# tps92512.net
KiCad netlist of a schematic drawn in EAGLE
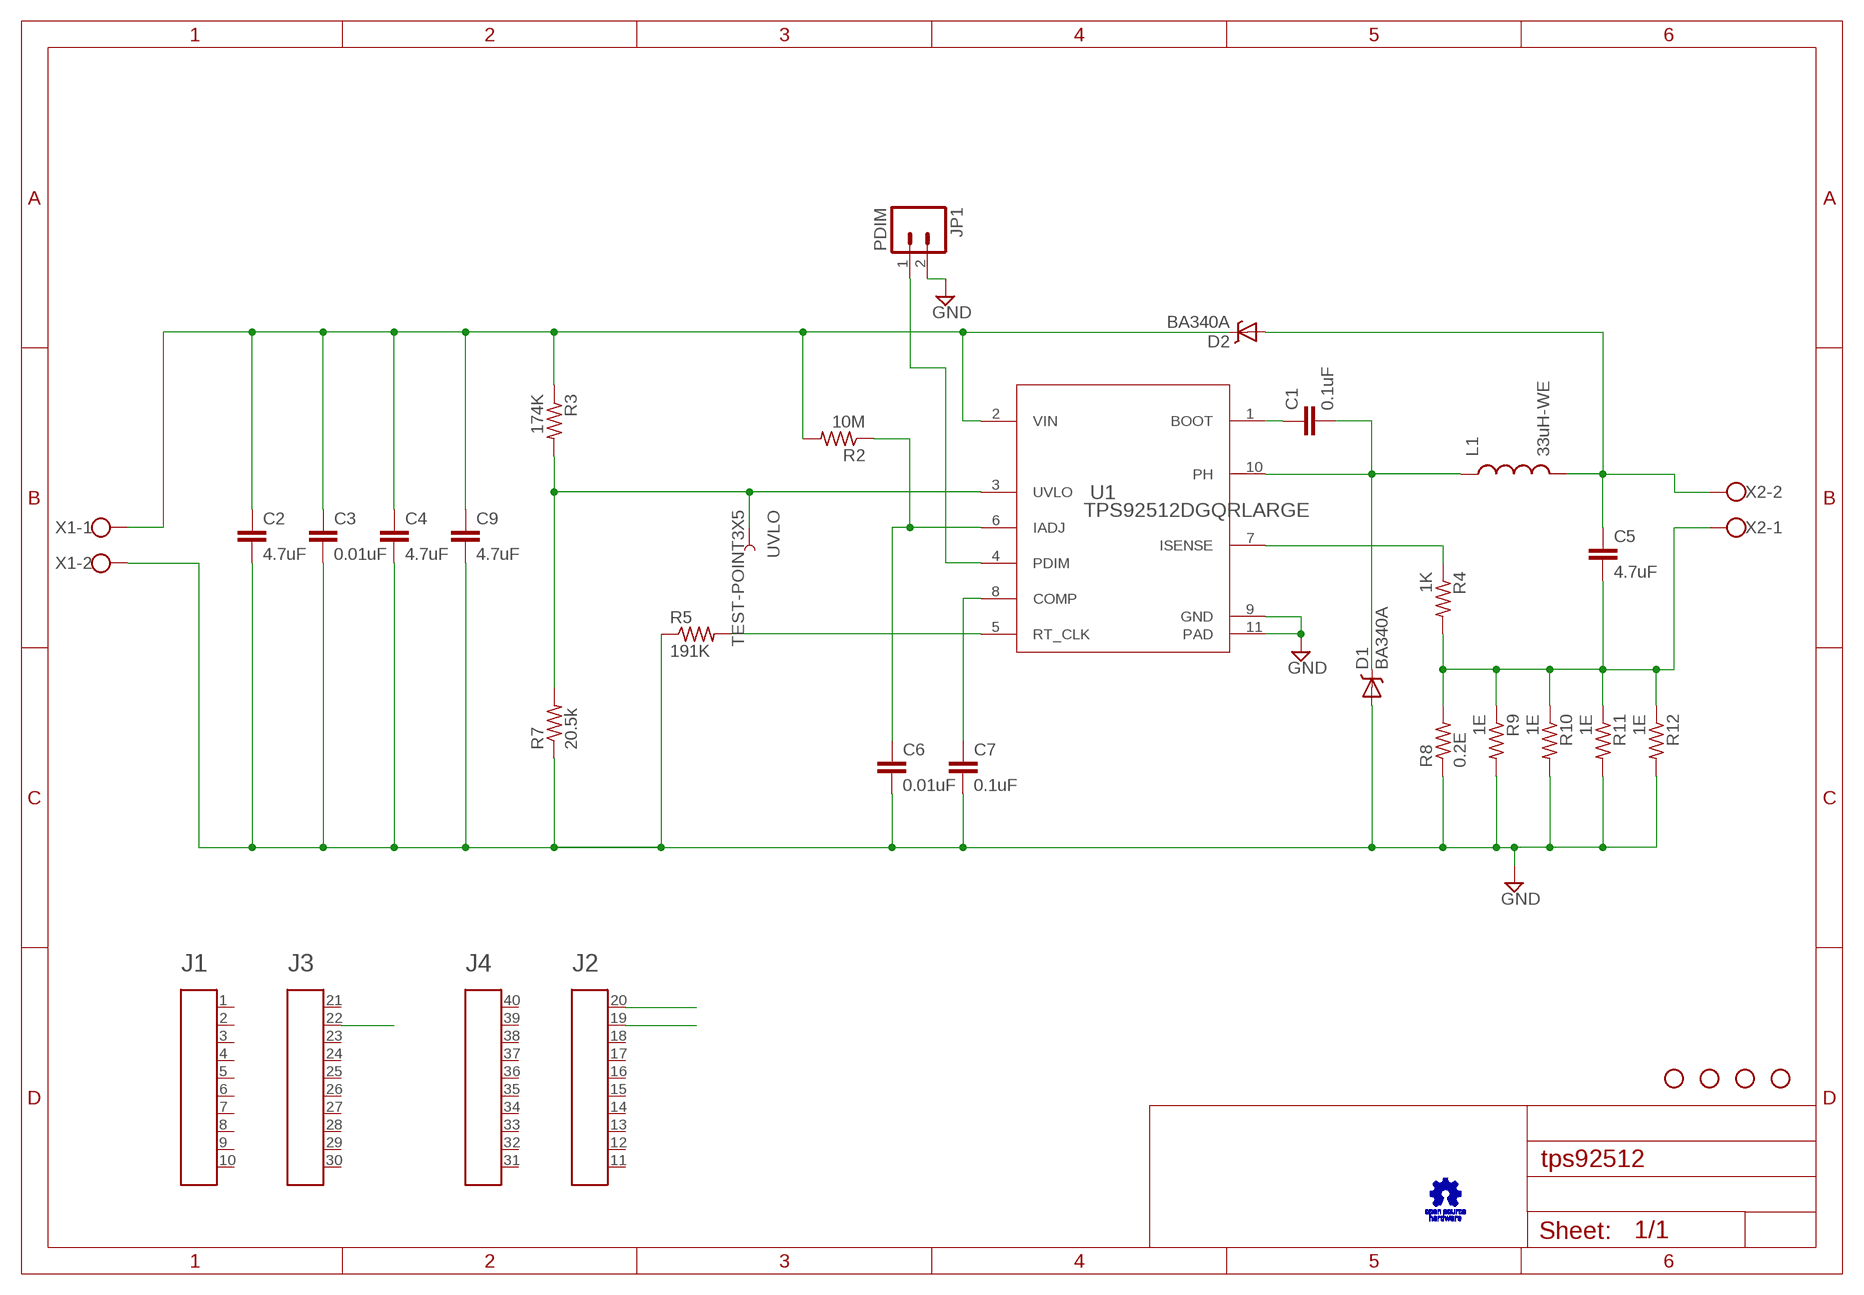
[diagram p0: schematic, sheet 1]

(export (version "E")
  (design (tool "Eeschema 10.0.6"))
  (components
    (comp (ref "A1")
      (value "HEADER4X10-BOOSTERPACK")
      (footprint "eagle-import:4X10-BOOSTERPACK")
      (libsource (lib "eagle-import") (part "HEADER4X10-BOOSTERPACK"))
    )
    (comp (ref "C1")
      (value "0.1uF")
      (footprint "eagle-import:0805")
      (libsource (lib "eagle-import") (part "CAP0805"))
    )
    (comp (ref "C2")
      (value "4.7uF")
      (footprint "eagle-import:1210")
      (libsource (lib "eagle-import") (part "10UF50V20%(1210)"))
    )
    (comp (ref "C3")
      (value "0.01uF")
      (footprint "eagle-import:0805")
      (libsource (lib "eagle-import") (part "CAP0805"))
    )
    (comp (ref "C4")
      (value "4.7uF")
      (footprint "eagle-import:1210")
      (libsource (lib "eagle-import") (part "10UF50V20%(1210)"))
    )
    (comp (ref "C5")
      (value "4.7uF")
      (footprint "eagle-import:1206")
      (libsource (lib "eagle-import") (part "10UF-6.3V-20%(1206)"))
    )
    (comp (ref "C6")
      (value "0.01uF")
      (footprint "eagle-import:0805")
      (libsource (lib "eagle-import") (part "CAP0805"))
    )
    (comp (ref "C7")
      (value "0.1uF")
      (footprint "eagle-import:0805")
      (libsource (lib "eagle-import") (part "CAP0805"))
    )
    (comp (ref "C9")
      (value "4.7uF")
      (footprint "eagle-import:1210")
      (libsource (lib "eagle-import") (part "10UF50V20%(1210)"))
    )
    (comp (ref "D1")
      (value "BA340A")
      (footprint "eagle-import:SMA-DIODE")
      (libsource (lib "eagle-import") (part "B340A"))
    )
    (comp (ref "D2")
      (value "BA340A")
      (footprint "eagle-import:SMA-DIODE")
      (libsource (lib "eagle-import") (part "B340A"))
    )
    (comp (ref "JP1")
      (value "PDIM")
      (footprint "eagle-import:1X02_LOCK")
      (libsource (lib "eagle-import") (part "M02LOCK"))
    )
    (comp (ref "L1")
      (value "33uH-WE")
      (footprint "eagle-import:DR1030")
      (libsource (lib "eagle-import") (part "INDUCTORDR1030"))
    )
    (comp (ref "R2")
      (value "10M")
      (footprint "eagle-import:R0805")
      (libsource (lib "eagle-import") (part "R-US_R0805"))
    )
    (comp (ref "R3")
      (value "174K")
      (footprint "eagle-import:R0805")
      (libsource (lib "eagle-import") (part "R-US_R0805"))
    )
    (comp (ref "R4")
      (value "1K")
      (footprint "eagle-import:R0805")
      (libsource (lib "eagle-import") (part "R-US_R0805"))
    )
    (comp (ref "R5")
      (value "191K")
      (footprint "eagle-import:R0805")
      (libsource (lib "eagle-import") (part "R-US_R0805"))
    )
    (comp (ref "R7")
      (value "20.5k")
      (footprint "eagle-import:R0805")
      (libsource (lib "eagle-import") (part "R-US_R0805"))
    )
    (comp (ref "R8")
      (value "0.2E")
      (footprint "eagle-import:R1210W")
      (libsource (lib "eagle-import") (part "R-US_R1210W"))
    )
    (comp (ref "R9")
      (value "1E")
      (footprint "eagle-import:R0805")
      (libsource (lib "eagle-import") (part "R-US_R0805"))
    )
    (comp (ref "R10")
      (value "1E")
      (footprint "eagle-import:R0805")
      (libsource (lib "eagle-import") (part "R-US_R0805"))
    )
    (comp (ref "R11")
      (value "1E")
      (footprint "eagle-import:R0805")
      (libsource (lib "eagle-import") (part "R-US_R0805"))
    )
    (comp (ref "R12")
      (value "1E")
      (footprint "eagle-import:R0805")
      (libsource (lib "eagle-import") (part "R-US_R0805"))
    )
    (comp (ref "STANDOFF1")
      (value "STAND-OFF")
      (footprint "eagle-import:STAND-OFF")
      (libsource (lib "eagle-import") (part "STAND-OFF"))
    )
    (comp (ref "STANDOFF2")
      (value "STAND-OFF")
      (footprint "eagle-import:STAND-OFF")
      (libsource (lib "eagle-import") (part "STAND-OFF"))
    )
    (comp (ref "STANDOFF3")
      (value "STAND-OFF")
      (footprint "eagle-import:STAND-OFF")
      (libsource (lib "eagle-import") (part "STAND-OFF"))
    )
    (comp (ref "STANDOFF4")
      (value "STAND-OFF")
      (footprint "eagle-import:STAND-OFF")
      (libsource (lib "eagle-import") (part "STAND-OFF"))
    )
    (comp (ref "U1")
      (value "TPS92512DGQRLARGE")
      (footprint "eagle-import:DGQ0010D_M")
      (libsource (lib "eagle-import") (part "TPS92512DGQRLARGE"))
    )
    (comp (ref "UVLO")
      (value "TEST-POINT3X5")
      (footprint "eagle-import:PAD.03X.05")
      (libsource (lib "eagle-import") (part "TEST-POINT3X5"))
    )
    (comp (ref "X1")
      (value "W237-102")
      (footprint "eagle-import:W237-102")
      (fields (field (name "MPN") "237-102"))
      (libsource (lib "eagle-import") (part "W237-102"))
    )
    (comp (ref "X2")
      (value "W237-102")
      (footprint "eagle-import:W237-102")
      (fields (field (name "MPN") "237-102"))
      (libsource (lib "eagle-import") (part "W237-102"))
    )
  )
  (nets
    (net (code "1") (name "/PDIM") (class "Default")
      (node (ref "A1") (pin "19") (pinfunction "P$19_19") (pintype "bidirectional"))
      (node (ref "JP1") (pin "1") (pinfunction "1_1") (pintype "passive"))
      (node (ref "U1") (pin "4") (pinfunction "PDIM_4") (pintype "input"))
    )
    (net (code "2") (name "GND") (class "Default")
      (node (ref "A1") (pin "20") (pinfunction "P$20_20") (pintype "bidirectional"))
      (node (ref "A1") (pin "22") (pinfunction "P$22_22") (pintype "bidirectional"))
      (node (ref "C2") (pin "2") (pinfunction "2_2") (pintype "passive"))
      (node (ref "C3") (pin "2") (pinfunction "2_2") (pintype "passive"))
      (node (ref "C4") (pin "2") (pinfunction "2_2") (pintype "passive"))
      (node (ref "C6") (pin "2") (pinfunction "2_2") (pintype "passive"))
      (node (ref "C7") (pin "2") (pinfunction "2_2") (pintype "passive"))
      (node (ref "C9") (pin "2") (pinfunction "2_2") (pintype "passive"))
      (node (ref "D1") (pin "A") (pinfunction "A_A") (pintype "passive"))
      (node (ref "JP1") (pin "2") (pinfunction "2_2") (pintype "passive"))
      (node (ref "R10") (pin "2") (pinfunction "2_2") (pintype "passive"))
      (node (ref "R11") (pin "2") (pinfunction "2_2") (pintype "passive"))
      (node (ref "R12") (pin "2") (pinfunction "2_2") (pintype "passive"))
      (node (ref "R5") (pin "1") (pinfunction "1_1") (pintype "passive"))
      (node (ref "R7") (pin "1") (pinfunction "1_1") (pintype "passive"))
      (node (ref "R8") (pin "1") (pinfunction "1_1") (pintype "passive"))
      (node (ref "R9") (pin "2") (pinfunction "2_2") (pintype "passive"))
      (node (ref "U1") (pin "11") (pinfunction "PAD_11") (pintype "power_in"))
      (node (ref "U1") (pin "9") (pinfunction "GND_9") (pintype "power_in"))
      (node (ref "X1") (pin "2") (pinfunction "KL_2") (pintype "passive"))
    )
    (net (code "3") (name "Net-(U1-BOOT)") (class "Default")
      (node (ref "C1") (pin "1") (pinfunction "1_1") (pintype "passive"))
      (node (ref "U1") (pin "1") (pinfunction "BOOT_1") (pintype "power_in"))
    )
    (net (code "4") (name "Net-(U1-COMP)") (class "Default")
      (node (ref "C7") (pin "1") (pinfunction "1_1") (pintype "passive"))
      (node (ref "U1") (pin "8") (pinfunction "COMP_8") (pintype "output"))
    )
    (net (code "5") (name "Net-(U1-IADJ)") (class "Default")
      (node (ref "C6") (pin "1") (pinfunction "1_1") (pintype "passive"))
      (node (ref "R2") (pin "1") (pinfunction "1_1") (pintype "passive"))
      (node (ref "U1") (pin "6") (pinfunction "IADJ_6") (pintype "input"))
    )
    (net (code "6") (name "Net-(U1-ISENSE)") (class "Default")
      (node (ref "R4") (pin "1") (pinfunction "1_1") (pintype "passive"))
      (node (ref "U1") (pin "7") (pinfunction "ISENSE_7") (pintype "input"))
    )
    (net (code "7") (name "Net-(U1-PH)") (class "Default")
      (node (ref "C1") (pin "2") (pinfunction "2_2") (pintype "passive"))
      (node (ref "D1") (pin "C") (pinfunction "C_C") (pintype "passive"))
      (node (ref "L1") (pin "1") (pinfunction "1_1") (pintype "passive"))
      (node (ref "U1") (pin "10") (pinfunction "PH_10") (pintype "power_in"))
    )
    (net (code "8") (name "Net-(U1-RT_CLK)") (class "Default")
      (node (ref "R5") (pin "2") (pinfunction "2_2") (pintype "passive"))
      (node (ref "U1") (pin "5") (pinfunction "RT_CLK_5") (pintype "input"))
    )
    (net (code "9") (name "Net-(U1-UVLO)") (class "Default")
      (node (ref "R3") (pin "2") (pinfunction "2_2") (pintype "passive"))
      (node (ref "R7") (pin "2") (pinfunction "2_2") (pintype "passive"))
      (node (ref "U1") (pin "3") (pinfunction "UVLO_3") (pintype "input"))
      (node (ref "UVLO") (pin "P$1") (pinfunction "1_P$1") (pintype "bidirectional"))
    )
    (net (code "10") (name "Net-(U1-VIN)") (class "Default")
      (node (ref "C2") (pin "1") (pinfunction "1_1") (pintype "passive"))
      (node (ref "C3") (pin "1") (pinfunction "1_1") (pintype "passive"))
      (node (ref "C4") (pin "1") (pinfunction "1_1") (pintype "passive"))
      (node (ref "C9") (pin "1") (pinfunction "1_1") (pintype "passive"))
      (node (ref "D2") (pin "C") (pinfunction "C_C") (pintype "passive"))
      (node (ref "R2") (pin "2") (pinfunction "2_2") (pintype "passive"))
      (node (ref "R3") (pin "1") (pinfunction "1_1") (pintype "passive"))
      (node (ref "U1") (pin "2") (pinfunction "VIN_2") (pintype "power_in"))
      (node (ref "X1") (pin "1") (pinfunction "KL_1") (pintype "passive"))
    )
    (net (code "11") (name "Net-(X2A-KL)") (class "Default")
      (node (ref "C5") (pin "2") (pinfunction "2_2") (pintype "passive"))
      (node (ref "R10") (pin "1") (pinfunction "1_1") (pintype "passive"))
      (node (ref "R11") (pin "1") (pinfunction "1_1") (pintype "passive"))
      (node (ref "R12") (pin "1") (pinfunction "1_1") (pintype "passive"))
      (node (ref "R4") (pin "2") (pinfunction "2_2") (pintype "passive"))
      (node (ref "R8") (pin "2") (pinfunction "2_2") (pintype "passive"))
      (node (ref "R9") (pin "1") (pinfunction "1_1") (pintype "passive"))
      (node (ref "X2") (pin "1") (pinfunction "KL_1") (pintype "passive"))
    )
    (net (code "12") (name "Net-(X2B-KL)") (class "Default")
      (node (ref "C5") (pin "1") (pinfunction "1_1") (pintype "passive"))
      (node (ref "D2") (pin "A") (pinfunction "A_A") (pintype "passive"))
      (node (ref "L1") (pin "2") (pinfunction "2_2") (pintype "passive"))
      (node (ref "X2") (pin "2") (pinfunction "KL_2") (pintype "passive"))
    )
    (net (code "13") (name "unconnected-(A1-P$1-Pad1)") (class "Default")
      (node (ref "A1") (pin "1") (pinfunction "P$1_1") (pintype "bidirectional"))
    )
    (net (code "14") (name "unconnected-(A1-P$2-Pad2)") (class "Default")
      (node (ref "A1") (pin "2") (pinfunction "P$2_2") (pintype "bidirectional"))
    )
    (net (code "15") (name "unconnected-(A1-P$3-Pad3)") (class "Default")
      (node (ref "A1") (pin "3") (pinfunction "P$3_3") (pintype "bidirectional"))
    )
    (net (code "16") (name "unconnected-(A1-P$4-Pad4)") (class "Default")
      (node (ref "A1") (pin "4") (pinfunction "P$4_4") (pintype "bidirectional"))
    )
    (net (code "17") (name "unconnected-(A1-P$5-Pad5)") (class "Default")
      (node (ref "A1") (pin "5") (pinfunction "P$5_5") (pintype "bidirectional"))
    )
    (net (code "18") (name "unconnected-(A1-P$6-Pad6)") (class "Default")
      (node (ref "A1") (pin "6") (pinfunction "P$6_6") (pintype "bidirectional"))
    )
    (net (code "19") (name "unconnected-(A1-P$7-Pad7)") (class "Default")
      (node (ref "A1") (pin "7") (pinfunction "P$7_7") (pintype "bidirectional"))
    )
    (net (code "20") (name "unconnected-(A1-P$8-Pad8)") (class "Default")
      (node (ref "A1") (pin "8") (pinfunction "P$8_8") (pintype "bidirectional"))
    )
    (net (code "21") (name "unconnected-(A1-P$9-Pad9)") (class "Default")
      (node (ref "A1") (pin "9") (pinfunction "P$9_9") (pintype "bidirectional"))
    )
    (net (code "22") (name "unconnected-(A1-P$10-Pad10)") (class "Default")
      (node (ref "A1") (pin "10") (pinfunction "P$10_10") (pintype "bidirectional"))
    )
    (net (code "23") (name "unconnected-(A1-P$11-Pad11)") (class "Default")
      (node (ref "A1") (pin "11") (pinfunction "P$11_11") (pintype "bidirectional"))
    )
    (net (code "24") (name "unconnected-(A1-P$12-Pad12)") (class "Default")
      (node (ref "A1") (pin "12") (pinfunction "P$12_12") (pintype "bidirectional"))
    )
    (net (code "25") (name "unconnected-(A1-P$13-Pad13)") (class "Default")
      (node (ref "A1") (pin "13") (pinfunction "P$13_13") (pintype "bidirectional"))
    )
    (net (code "26") (name "unconnected-(A1-P$14-Pad14)") (class "Default")
      (node (ref "A1") (pin "14") (pinfunction "P$14_14") (pintype "bidirectional"))
    )
    (net (code "27") (name "unconnected-(A1-P$15-Pad15)") (class "Default")
      (node (ref "A1") (pin "15") (pinfunction "P$15_15") (pintype "bidirectional"))
    )
    (net (code "28") (name "unconnected-(A1-P$16-Pad16)") (class "Default")
      (node (ref "A1") (pin "16") (pinfunction "P$16_16") (pintype "bidirectional"))
    )
    (net (code "29") (name "unconnected-(A1-P$17-Pad17)") (class "Default")
      (node (ref "A1") (pin "17") (pinfunction "P$17_17") (pintype "bidirectional"))
    )
    (net (code "30") (name "unconnected-(A1-P$18-Pad18)") (class "Default")
      (node (ref "A1") (pin "18") (pinfunction "P$18_18") (pintype "bidirectional"))
    )
    (net (code "31") (name "unconnected-(A1-P$21-Pad21)") (class "Default")
      (node (ref "A1") (pin "21") (pinfunction "P$21_21") (pintype "bidirectional"))
    )
    (net (code "32") (name "unconnected-(A1-P$23-Pad23)") (class "Default")
      (node (ref "A1") (pin "23") (pinfunction "P$23_23") (pintype "bidirectional"))
    )
    (net (code "33") (name "unconnected-(A1-P$24-Pad24)") (class "Default")
      (node (ref "A1") (pin "24") (pinfunction "P$24_24") (pintype "bidirectional"))
    )
    (net (code "34") (name "unconnected-(A1-P$25-Pad25)") (class "Default")
      (node (ref "A1") (pin "25") (pinfunction "P$25_25") (pintype "bidirectional"))
    )
    (net (code "35") (name "unconnected-(A1-P$26-Pad26)") (class "Default")
      (node (ref "A1") (pin "26") (pinfunction "P$26_26") (pintype "bidirectional"))
    )
    (net (code "36") (name "unconnected-(A1-P$27-Pad27)") (class "Default")
      (node (ref "A1") (pin "27") (pinfunction "P$27_27") (pintype "bidirectional"))
    )
    (net (code "37") (name "unconnected-(A1-P$28-Pad28)") (class "Default")
      (node (ref "A1") (pin "28") (pinfunction "P$28_28") (pintype "bidirectional"))
    )
    (net (code "38") (name "unconnected-(A1-P$29-Pad29)") (class "Default")
      (node (ref "A1") (pin "29") (pinfunction "P$29_29") (pintype "bidirectional"))
    )
    (net (code "39") (name "unconnected-(A1-P$30-Pad30)") (class "Default")
      (node (ref "A1") (pin "30") (pinfunction "P$30_30") (pintype "bidirectional"))
    )
    (net (code "40") (name "unconnected-(A1-P$31-Pad31)") (class "Default")
      (node (ref "A1") (pin "31") (pinfunction "P$31_31") (pintype "bidirectional"))
    )
    (net (code "41") (name "unconnected-(A1-P$32-Pad32)") (class "Default")
      (node (ref "A1") (pin "32") (pinfunction "P$32_32") (pintype "bidirectional"))
    )
    (net (code "42") (name "unconnected-(A1-P$33-Pad33)") (class "Default")
      (node (ref "A1") (pin "33") (pinfunction "P$33_33") (pintype "bidirectional"))
    )
    (net (code "43") (name "unconnected-(A1-P$34-Pad34)") (class "Default")
      (node (ref "A1") (pin "34") (pinfunction "P$34_34") (pintype "bidirectional"))
    )
    (net (code "44") (name "unconnected-(A1-P$35-Pad35)") (class "Default")
      (node (ref "A1") (pin "35") (pinfunction "P$35_35") (pintype "bidirectional"))
    )
    (net (code "45") (name "unconnected-(A1-P$36-Pad36)") (class "Default")
      (node (ref "A1") (pin "36") (pinfunction "P$36_36") (pintype "bidirectional"))
    )
    (net (code "46") (name "unconnected-(A1-P$37-Pad37)") (class "Default")
      (node (ref "A1") (pin "37") (pinfunction "P$37_37") (pintype "bidirectional"))
    )
    (net (code "47") (name "unconnected-(A1-P$38-Pad38)") (class "Default")
      (node (ref "A1") (pin "38") (pinfunction "P$38_38") (pintype "bidirectional"))
    )
    (net (code "48") (name "unconnected-(A1-P$39-Pad39)") (class "Default")
      (node (ref "A1") (pin "39") (pinfunction "P$39_39") (pintype "bidirectional"))
    )
    (net (code "49") (name "unconnected-(A1-P$40-Pad40)") (class "Default")
      (node (ref "A1") (pin "40") (pinfunction "P$40_40") (pintype "bidirectional"))
    )
  )
)
